# Stand_Alone_Inv_Adapter.net
KiCad netlist of a schematic drawn in EAGLE
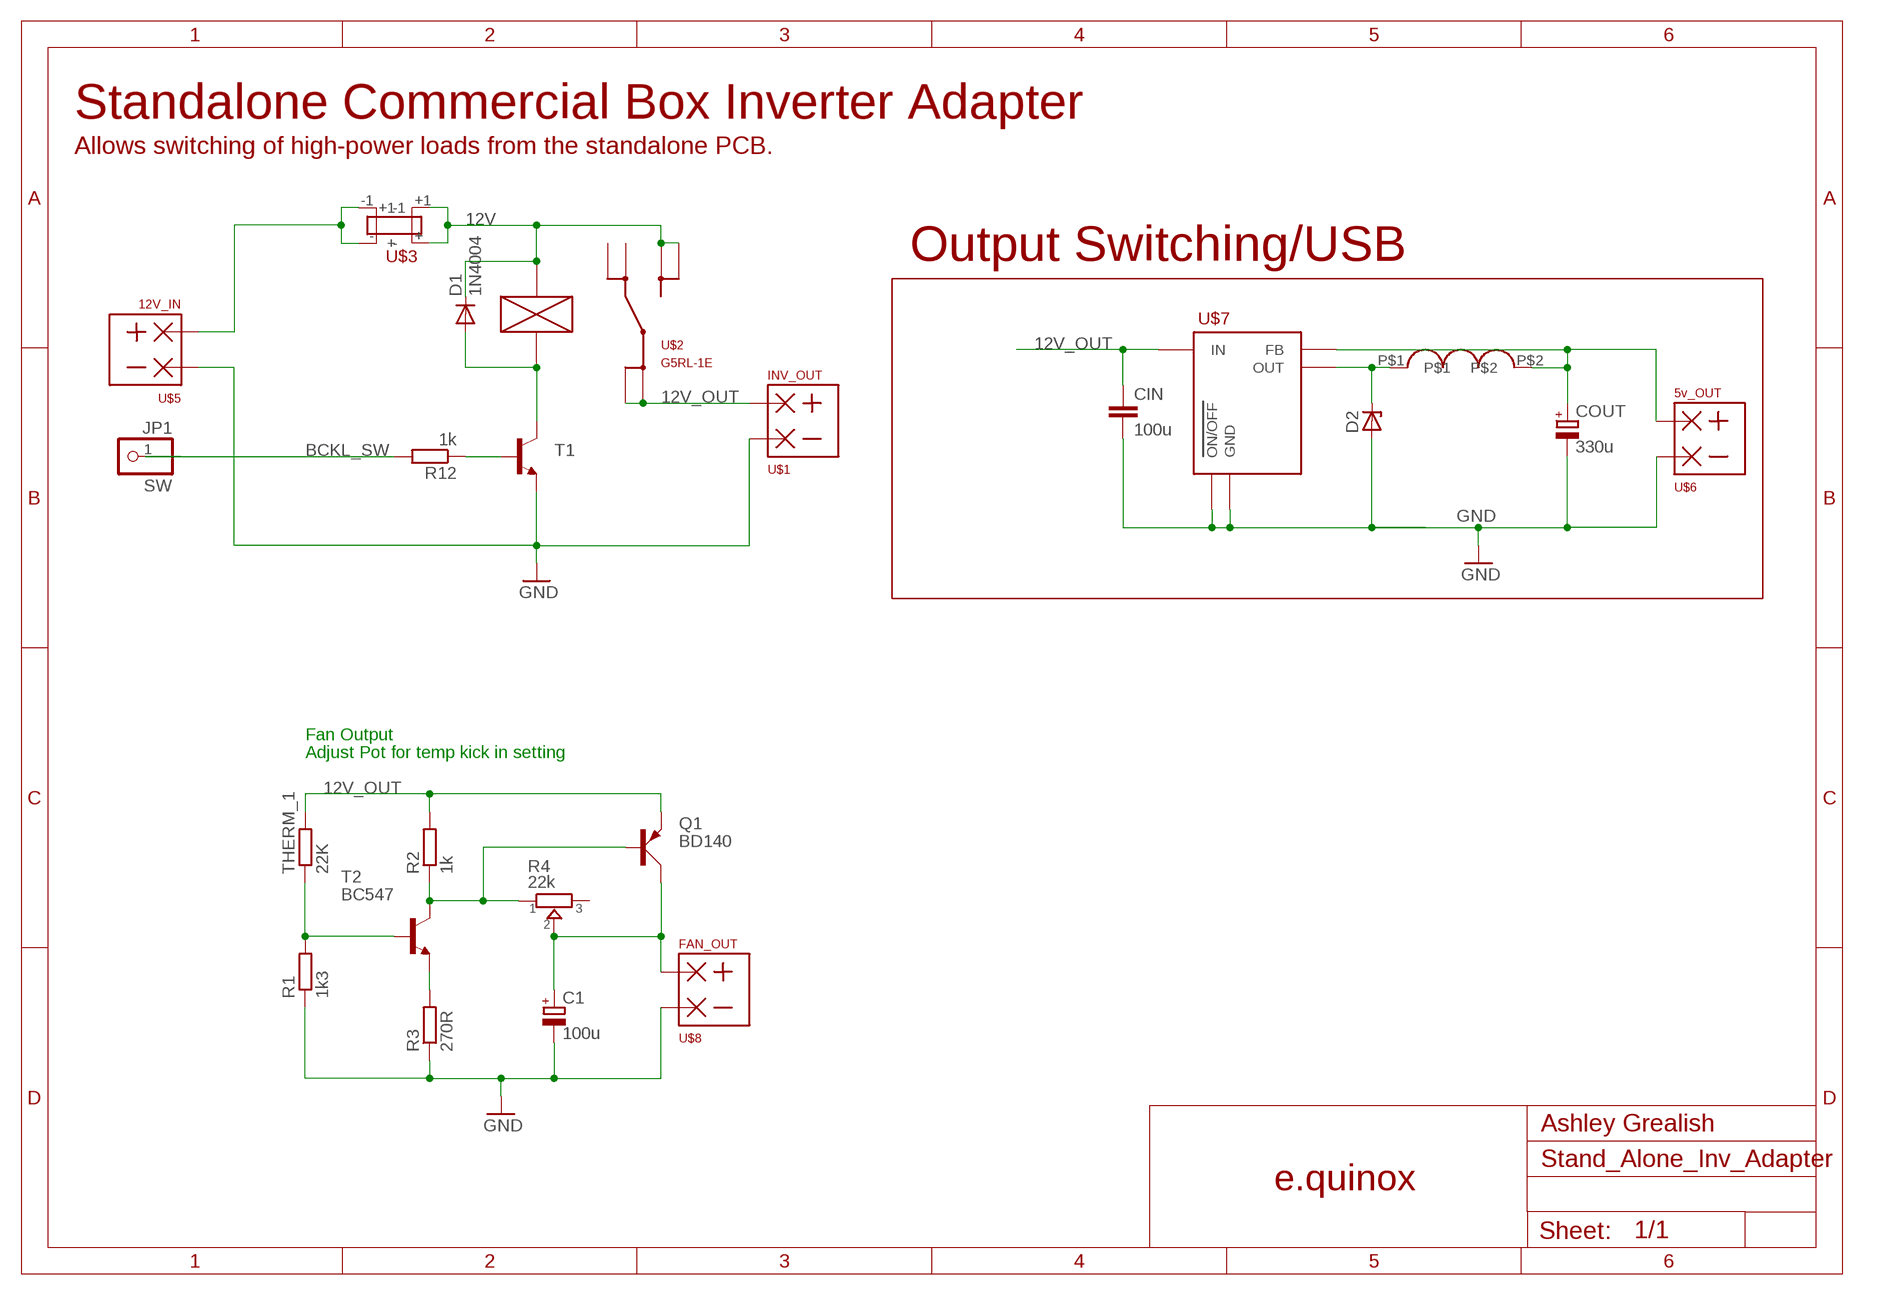
[diagram p0: schematic, sheet 1]

(export (version "E")
  (design (tool "Eeschema 10.0.6"))
  (components
    (comp (ref "C1")
      (value "100u")
      (footprint "eagle-import:B45181B")
      (libsource (lib "eagle-import") (part "CPOL-EUB45181B"))
    )
    (comp (ref "CIN")
      (value "100u")
      (footprint "eagle-import:C2.5-2")
      (libsource (lib "eagle-import") (part "C2.5/2"))
    )
    (comp (ref "COUT")
      (value "330u")
      (footprint "eagle-import:B45181D")
      (libsource (lib "eagle-import") (part "CPOL-EUB45181D"))
    )
    (comp (ref "D1")
      (value "1N4004")
      (footprint "eagle-import:DO41-10")
      (libsource (lib "eagle-import") (part "1N4004"))
    )
    (comp (ref "D2")
      (value "ZENER-DIODEDO41Z10")
      (footprint "eagle-import:DO41Z10")
      (libsource (lib "eagle-import") (part "ZENER-DIODEDO41Z10"))
    )
    (comp (ref "JP1")
      (value "SW")
      (footprint "eagle-import:1X01")
      (libsource (lib "eagle-import") (part "PINHD-1X1"))
    )
    (comp (ref "Q1")
      (value "BD140")
      (footprint "eagle-import:TO126AV")
      (libsource (lib "eagle-import") (part "BD140"))
    )
    (comp (ref "R1")
      (value "1k3")
      (footprint "eagle-import:0207_10")
      (libsource (lib "eagle-import") (part "R-EU_0207/10"))
    )
    (comp (ref "R2")
      (value "1k")
      (footprint "eagle-import:0207_10")
      (libsource (lib "eagle-import") (part "R-EU_0207/10"))
    )
    (comp (ref "R3")
      (value "270R")
      (footprint "eagle-import:0207_10")
      (libsource (lib "eagle-import") (part "R-EU_0207/10"))
    )
    (comp (ref "R4")
      (value "22k")
      (footprint "eagle-import:TRIMMER_3362P")
      (libsource (lib "eagle-import") (part "TRIMMER-3362P"))
    )
    (comp (ref "R12")
      (value "1k")
      (footprint "eagle-import:RTH025W")
      (libsource (lib "eagle-import") (part "RESISTOR-PTH-0.4"))
    )
    (comp (ref "T1")
      (value "BC546-NPN-TO92-CBE")
      (footprint "eagle-import:TO92-CBE")
      (libsource (lib "eagle-import") (part "-NPN-TO92-CBEBC546"))
    )
    (comp (ref "T2")
      (value "BC547")
      (footprint "eagle-import:TO92")
      (libsource (lib "eagle-import") (part "BC547"))
    )
    (comp (ref "THERM_1")
      (value "22K")
      (footprint "eagle-import:0204_7")
      (libsource (lib "eagle-import") (part "R-EU_0204/7"))
    )
    (comp (ref "U$1")
      (value "INV_OUT")
      (footprint "eagle-import:TERMINAL_2WAY")
      (libsource (lib "eagle-import") (part "TERMINAL_2WAY"))
    )
    (comp (ref "U$2")
      (value "G5RL-1E")
      (footprint "eagle-import:G5RL-1E")
      (libsource (lib "eagle-import") (part "G5RL-1E"))
    )
    (comp (ref "U$3")
      (value "EQBX_FUSEEQBX_FUSE")
      (footprint "eagle-import:EQBX_FUSE")
      (libsource (lib "eagle-import") (part "EQBX_FUSEEQBX_FUSE"))
    )
    (comp (ref "U$4")
      (value "EQBX_INDUCTOR2")
      (footprint "eagle-import:INDUCTOR")
      (libsource (lib "eagle-import") (part "EQBX_INDUCTOR2"))
    )
    (comp (ref "U$5")
      (value "12V_IN")
      (footprint "eagle-import:TERMINAL_2WAY")
      (libsource (lib "eagle-import") (part "TERMINAL_2WAY"))
    )
    (comp (ref "U$6")
      (value "5v_OUT")
      (footprint "eagle-import:TERMINAL_2WAY")
      (libsource (lib "eagle-import") (part "TERMINAL_2WAY"))
    )
    (comp (ref "U$7")
      (value "LM2575")
      (footprint "eagle-import:TO220-5")
      (libsource (lib "eagle-import") (part "LM2575"))
    )
    (comp (ref "U$8")
      (value "FAN_OUT")
      (footprint "eagle-import:TERMINAL_2WAY")
      (libsource (lib "eagle-import") (part "TERMINAL_2WAY"))
    )
  )
  (nets
    (net (code "1") (name "/12V") (class "Default")
      (node (ref "D1") (pin "C") (pinfunction "C_C") (pintype "passive"))
      (node (ref "U$2") (pin "COIL+") (pinfunction "COIL+_COIL+") (pintype "bidirectional"))
      (node (ref "U$2") (pin "NO@1") (pinfunction "NO_NO@1") (pintype "bidirectional"))
      (node (ref "U$2") (pin "NO@2") (pinfunction "NO_NO@2") (pintype "bidirectional"))
      (node (ref "U$3") (pin "+") (pinfunction "+_+") (pintype "bidirectional"))
      (node (ref "U$3") (pin "+1") (pinfunction "+1_+1") (pintype "bidirectional"))
    )
    (net (code "2") (name "/12V_OUT") (class "Default")
      (node (ref "CIN") (pin "1") (pinfunction "1_1") (pintype "passive"))
      (node (ref "Q1") (pin "E") (pinfunction "E_E") (pintype "passive"))
      (node (ref "R2") (pin "2") (pinfunction "2_2") (pintype "passive"))
      (node (ref "THERM_1") (pin "2") (pinfunction "2_2") (pintype "passive"))
      (node (ref "U$1") (pin "P$1") (pinfunction "P$1_P$1") (pintype "bidirectional"))
      (node (ref "U$2") (pin "COM@1") (pinfunction "COM_COM@1") (pintype "bidirectional"))
      (node (ref "U$2") (pin "COM@2") (pinfunction "COM_COM@2") (pintype "bidirectional"))
      (node (ref "U$7") (pin "P$1") (pinfunction "IN_P$1") (pintype "bidirectional"))
    )
    (net (code "3") (name "/BCKL_SW") (class "Default")
      (node (ref "JP1") (pin "1") (pinfunction "1_1") (pintype "passive"))
      (node (ref "R12") (pin "2") (pinfunction "2_2") (pintype "passive"))
    )
    (net (code "4") (name "GND") (class "Default")
      (node (ref "C1") (pin "-") (pinfunction "-_-") (pintype "passive"))
      (node (ref "CIN") (pin "2") (pinfunction "2_2") (pintype "passive"))
      (node (ref "COUT") (pin "-") (pinfunction "-_-") (pintype "passive"))
      (node (ref "D2") (pin "A") (pinfunction "A_A") (pintype "passive"))
      (node (ref "R1") (pin "1") (pinfunction "1_1") (pintype "passive"))
      (node (ref "R3") (pin "1") (pinfunction "1_1") (pintype "passive"))
      (node (ref "T1") (pin "E") (pinfunction "E_E") (pintype "passive"))
      (node (ref "U$1") (pin "P$2") (pinfunction "P$2_P$2") (pintype "bidirectional"))
      (node (ref "U$5") (pin "P$2") (pinfunction "P$2_P$2") (pintype "bidirectional"))
      (node (ref "U$6") (pin "P$2") (pinfunction "P$2_P$2") (pintype "bidirectional"))
      (node (ref "U$7") (pin "P$3") (pinfunction "GND_P$3") (pintype "bidirectional"))
      (node (ref "U$7") (pin "P$5") (pinfunction "ON/OFF_P$5") (pintype "bidirectional"))
      (node (ref "U$8") (pin "P$2") (pinfunction "P$2_P$2") (pintype "bidirectional"))
    )
    (net (code "5") (name "Net-(C1-Pad+)") (class "Default")
      (node (ref "C1") (pin "+") (pinfunction "+_+") (pintype "passive"))
      (node (ref "Q1") (pin "C") (pinfunction "C_C") (pintype "passive"))
      (node (ref "R4") (pin "2") (pinfunction "2_2") (pintype "passive"))
      (node (ref "U$8") (pin "P$1") (pinfunction "P$1_P$1") (pintype "bidirectional"))
    )
    (net (code "6") (name "Net-(D1-PadA)") (class "Default")
      (node (ref "D1") (pin "A") (pinfunction "A_A") (pintype "passive"))
      (node (ref "T1") (pin "C") (pinfunction "C_C") (pintype "passive"))
      (node (ref "U$2") (pin "COIL-") (pinfunction "COIL-_COIL-") (pintype "bidirectional"))
    )
    (net (code "7") (name "Net-(R12-Pad1)") (class "Default")
      (node (ref "R12") (pin "1") (pinfunction "1_1") (pintype "passive"))
      (node (ref "T1") (pin "B") (pinfunction "B_B") (pintype "passive"))
    )
    (net (code "8") (name "Net-(T2-B)") (class "Default")
      (node (ref "R1") (pin "2") (pinfunction "2_2") (pintype "passive"))
      (node (ref "T2") (pin "2") (pinfunction "B_2") (pintype "passive"))
      (node (ref "THERM_1") (pin "1") (pinfunction "1_1") (pintype "passive"))
    )
    (net (code "9") (name "Net-(T2-C)") (class "Default")
      (node (ref "Q1") (pin "B") (pinfunction "B_B") (pintype "passive"))
      (node (ref "R2") (pin "1") (pinfunction "1_1") (pintype "passive"))
      (node (ref "R4") (pin "1") (pinfunction "1_1") (pintype "passive"))
      (node (ref "T2") (pin "3") (pinfunction "C_3") (pintype "passive"))
    )
    (net (code "10") (name "Net-(T2-E)") (class "Default")
      (node (ref "R3") (pin "2") (pinfunction "2_2") (pintype "passive"))
      (node (ref "T2") (pin "1") (pinfunction "E_1") (pintype "passive"))
    )
    (net (code "11") (name "Net-(U$3-Pad-)") (class "Default")
      (node (ref "U$3") (pin "-") (pinfunction "-_-") (pintype "bidirectional"))
      (node (ref "U$3") (pin "-1") (pinfunction "-1_-1") (pintype "bidirectional"))
      (node (ref "U$5") (pin "P$1") (pinfunction "P$1_P$1") (pintype "bidirectional"))
    )
    (net (code "12") (name "Net-(U$7-FB)") (class "Default")
      (node (ref "COUT") (pin "+") (pinfunction "+_+") (pintype "passive"))
      (node (ref "U$4") (pin "P$2") (pinfunction "P$2_P$2") (pintype "bidirectional"))
      (node (ref "U$6") (pin "P$1") (pinfunction "P$1_P$1") (pintype "bidirectional"))
      (node (ref "U$7") (pin "P$4") (pinfunction "FB_P$4") (pintype "bidirectional"))
    )
    (net (code "13") (name "Net-(U$7-OUT)") (class "Default")
      (node (ref "D2") (pin "C") (pinfunction "C_C") (pintype "passive"))
      (node (ref "U$4") (pin "P$1") (pinfunction "P$1_P$1") (pintype "bidirectional"))
      (node (ref "U$7") (pin "P$2") (pinfunction "OUT_P$2") (pintype "bidirectional"))
    )
    (net (code "14") (name "unconnected-(R4-Pad3)") (class "Default")
      (node (ref "R4") (pin "3") (pinfunction "3_3") (pintype "passive"))
    )
    (net (code "15") (name "unconnected-(U$2-NC-PadNC@1)") (class "Default")
      (node (ref "U$2") (pin "NC@1") (pinfunction "NC_NC@1") (pintype "bidirectional"))
    )
    (net (code "16") (name "unconnected-(U$2-NC-PadNC@2)") (class "Default")
      (node (ref "U$2") (pin "NC@2") (pinfunction "NC_NC@2") (pintype "bidirectional"))
    )
  )
)
